# tms-rgb.net
KiCad netlist of a schematic drawn in EAGLE
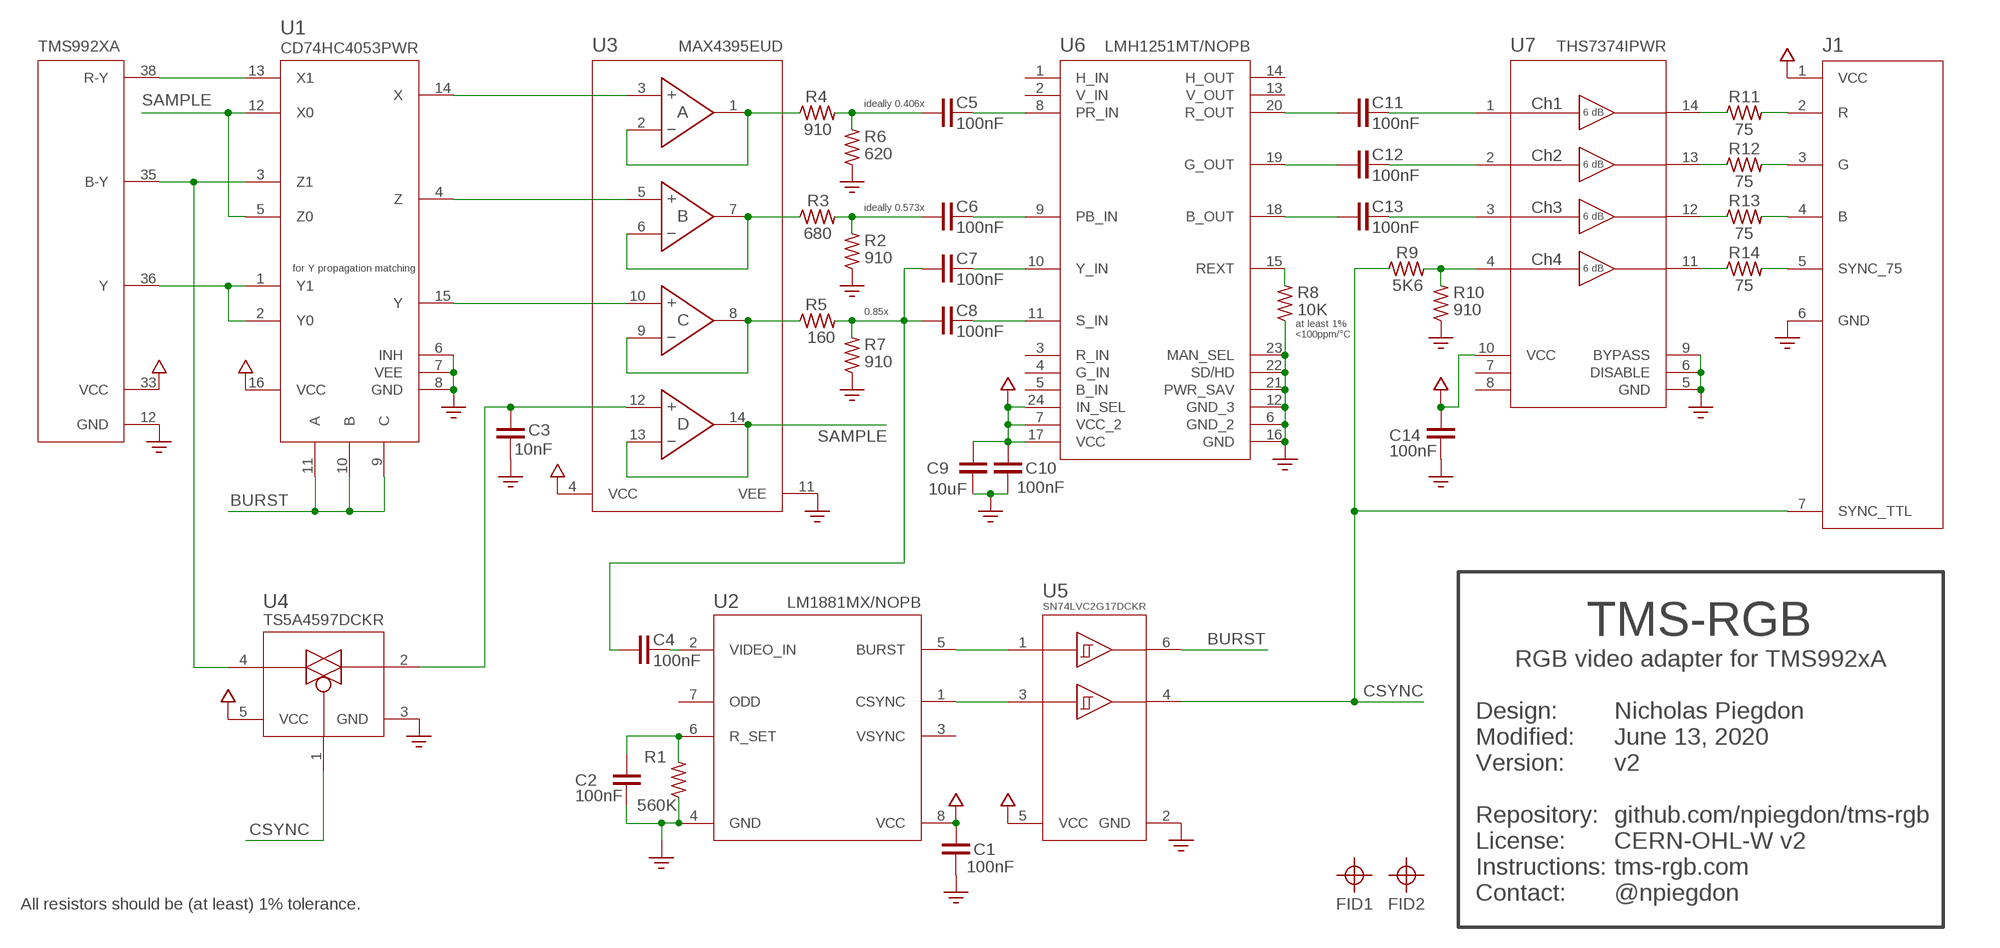
[diagram p0: schematic, sheet 1]

(export (version "E")
  (design (tool "Eeschema 10.0.6"))
  (components
    (comp (ref "C1")
      (value "100nF")
      (footprint "eagle-import:C0603")
      (libsource (lib "eagle-import") (part "C0603"))
    )
    (comp (ref "C2")
      (value "100nF")
      (footprint "eagle-import:C0603")
      (libsource (lib "eagle-import") (part "C0603"))
    )
    (comp (ref "C3")
      (value "10nF")
      (footprint "eagle-import:C0603")
      (libsource (lib "eagle-import") (part "C0603"))
    )
    (comp (ref "C4")
      (value "100nF")
      (footprint "eagle-import:C0603")
      (libsource (lib "eagle-import") (part "C0603"))
    )
    (comp (ref "C5")
      (value "100nF")
      (footprint "eagle-import:C0603")
      (libsource (lib "eagle-import") (part "C0603"))
    )
    (comp (ref "C6")
      (value "100nF")
      (footprint "eagle-import:C0603")
      (libsource (lib "eagle-import") (part "C0603"))
    )
    (comp (ref "C7")
      (value "100nF")
      (footprint "eagle-import:C0603")
      (libsource (lib "eagle-import") (part "C0603"))
    )
    (comp (ref "C8")
      (value "100nF")
      (footprint "eagle-import:C0603")
      (libsource (lib "eagle-import") (part "C0603"))
    )
    (comp (ref "C9")
      (value "10uF")
      (footprint "eagle-import:C1206")
      (libsource (lib "eagle-import") (part "C1206"))
    )
    (comp (ref "C10")
      (value "100nF")
      (footprint "eagle-import:C0603")
      (libsource (lib "eagle-import") (part "C0603"))
    )
    (comp (ref "C11")
      (value "100nF")
      (footprint "eagle-import:C0603")
      (libsource (lib "eagle-import") (part "C0603"))
    )
    (comp (ref "C12")
      (value "100nF")
      (footprint "eagle-import:C0603")
      (libsource (lib "eagle-import") (part "C0603"))
    )
    (comp (ref "C13")
      (value "100nF")
      (footprint "eagle-import:C0603")
      (libsource (lib "eagle-import") (part "C0603"))
    )
    (comp (ref "C14")
      (value "100nF")
      (footprint "eagle-import:C0603")
      (libsource (lib "eagle-import") (part "C0603"))
    )
    (comp (ref "FID1")
      (value "FIDUCIAL")
      (footprint "eagle-import:FIDUCIAL")
      (libsource (lib "eagle-import") (part "FIDUCIAL"))
    )
    (comp (ref "FID2")
      (value "FIDUCIAL")
      (footprint "eagle-import:FIDUCIAL")
      (libsource (lib "eagle-import") (part "FIDUCIAL"))
    )
    (comp (ref "J1")
      (value "Pads")
      (footprint "eagle-import:PADS")
      (libsource (lib "eagle-import") (part "PADSRGB"))
    )
    (comp (ref "R1")
      (value "560K")
      (footprint "eagle-import:R0603")
      (libsource (lib "eagle-import") (part "R0603"))
    )
    (comp (ref "R2")
      (value "910")
      (footprint "eagle-import:R0603")
      (libsource (lib "eagle-import") (part "R0603"))
    )
    (comp (ref "R3")
      (value "680")
      (footprint "eagle-import:R0603")
      (libsource (lib "eagle-import") (part "R0603"))
    )
    (comp (ref "R4")
      (value "910")
      (footprint "eagle-import:R0603")
      (libsource (lib "eagle-import") (part "R0603"))
    )
    (comp (ref "R5")
      (value "160")
      (footprint "eagle-import:R0603")
      (libsource (lib "eagle-import") (part "R0603"))
    )
    (comp (ref "R6")
      (value "620")
      (footprint "eagle-import:R0603")
      (libsource (lib "eagle-import") (part "R0603"))
    )
    (comp (ref "R7")
      (value "910")
      (footprint "eagle-import:R0603")
      (libsource (lib "eagle-import") (part "R0603"))
    )
    (comp (ref "R8")
      (value "10K")
      (footprint "eagle-import:R0603")
      (libsource (lib "eagle-import") (part "R0603"))
    )
    (comp (ref "R9")
      (value "5K6")
      (footprint "eagle-import:R0603")
      (libsource (lib "eagle-import") (part "R0603"))
    )
    (comp (ref "R10")
      (value "910")
      (footprint "eagle-import:R0603")
      (libsource (lib "eagle-import") (part "R0603"))
    )
    (comp (ref "R11")
      (value "75")
      (footprint "eagle-import:R0603")
      (libsource (lib "eagle-import") (part "R0603"))
    )
    (comp (ref "R12")
      (value "75")
      (footprint "eagle-import:R0603")
      (libsource (lib "eagle-import") (part "R0603"))
    )
    (comp (ref "R13")
      (value "75")
      (footprint "eagle-import:R0603")
      (libsource (lib "eagle-import") (part "R0603"))
    )
    (comp (ref "R14")
      (value "75")
      (footprint "eagle-import:R0603")
      (libsource (lib "eagle-import") (part "R0603"))
    )
    (comp (ref "U1")
      (value "CD74HC4053PWR")
      (footprint "eagle-import:CD74HC4053")
      (fields (field (name "MANUFACTURER") "Texas Instruments"))
      (libsource (lib "eagle-import") (part "CD74HC4053PWR"))
    )
    (comp (ref "U2")
      (value "LM1881MX/NOPB")
      (footprint "eagle-import:LM1881")
      (libsource (lib "eagle-import") (part "LM1881MX/NOPB"))
    )
    (comp (ref "U3")
      (value "MAX4395EUD")
      (footprint "eagle-import:MAX4395")
      (fields (field (name "MANUFACTURER_PART_NUMBER") "max4395eud+"))
      (libsource (lib "eagle-import") (part "MAX4395EUD"))
    )
    (comp (ref "U4")
      (value "TS5A4597DCKR")
      (footprint "eagle-import:DCK5")
      (fields
        (field (name "GENERIC_PART_NUMBER") "TS5A4597")
        (field (name "MANUFACTURER") "Texas Instruments")
      )
      (libsource (lib "eagle-import") (part "TS5A4597DCKR"))
    )
    (comp (ref "U5")
      (value "SN74LVC2G17DCKR")
      (footprint "eagle-import:DCK6")
      (fields (field (name "MANUFACTURER") "Texas Instruments"))
      (libsource (lib "eagle-import") (part "SN74LVC2G17DCKR"))
    )
    (comp (ref "U6")
      (value "LMH1251MT/NOPB")
      (footprint "eagle-import:LMH1251")
      (libsource (lib "eagle-import") (part "LMH1251MT/NOPB"))
    )
    (comp (ref "U7")
      (value "THS7374IPWR")
      (footprint "eagle-import:THS7374")
      (fields (field (name "MANUFACTURER") "Texas Instruments"))
      (libsource (lib "eagle-import") (part "THS7374IPWR"))
    )
    (comp (ref "U100")
      (value "TMS992XA")
      (footprint "eagle-import:TMS992XA")
      (libsource (lib "eagle-import") (part "TMS992XA"))
    )
  )
  (nets
    (net (code "1") (name "/BURST") (class "Default")
      (node (ref "U1") (pin "10") (pinfunction "B_10") (pintype "input"))
      (node (ref "U1") (pin "11") (pinfunction "A_11") (pintype "input"))
      (node (ref "U1") (pin "9") (pinfunction "C_9") (pintype "input"))
      (node (ref "U5") (pin "6") (pinfunction "1Y_6") (pintype "output"))
    )
    (net (code "2") (name "/CSYNC") (class "Default")
      (node (ref "J1") (pin "7") (pinfunction "SYNC_TTL_7") (pintype "passive"))
      (node (ref "R9") (pin "1") (pinfunction "1_1") (pintype "passive"))
      (node (ref "U4") (pin "1") (pinfunction "IN_1") (pintype "input"))
      (node (ref "U5") (pin "4") (pinfunction "2Y_4") (pintype "output"))
    )
    (net (code "3") (name "/SAMPLE") (class "Default")
      (node (ref "U1") (pin "12") (pinfunction "X0_12") (pintype "bidirectional"))
      (node (ref "U1") (pin "5") (pinfunction "Z0_5") (pintype "bidirectional"))
      (node (ref "U3") (pin "13") (pinfunction "D-_13") (pintype "input"))
      (node (ref "U3") (pin "14") (pinfunction "D_14") (pintype "output"))
    )
    (net (code "4") (name "5V") (class "Default")
      (node (ref "C1") (pin "1") (pinfunction "1_1") (pintype "passive"))
      (node (ref "C10") (pin "1") (pinfunction "1_1") (pintype "passive"))
      (node (ref "C14") (pin "1") (pinfunction "1_1") (pintype "passive"))
      (node (ref "C9") (pin "1") (pinfunction "1_1") (pintype "passive"))
      (node (ref "J1") (pin "1") (pinfunction "VCC_1") (pintype "passive"))
      (node (ref "U1") (pin "16") (pinfunction "VCC_16") (pintype "power_in"))
      (node (ref "U100") (pin "33") (pinfunction "VCC_33") (pintype "power_in"))
      (node (ref "U2") (pin "8") (pinfunction "VCC_8") (pintype "power_in"))
      (node (ref "U3") (pin "4") (pinfunction "VCC_4") (pintype "power_in"))
      (node (ref "U4") (pin "5") (pinfunction "VCC_5") (pintype "power_in"))
      (node (ref "U5") (pin "5") (pinfunction "VCC_5") (pintype "power_in"))
      (node (ref "U6") (pin "17") (pinfunction "VCC_17") (pintype "passive"))
      (node (ref "U6") (pin "24") (pinfunction "IN_SEL_24") (pintype "input"))
      (node (ref "U6") (pin "7") (pinfunction "VCC_2_7") (pintype "passive"))
      (node (ref "U7") (pin "10") (pinfunction "VCC_10") (pintype "power_in"))
    )
    (net (code "5") (name "GND") (class "Default")
      (node (ref "C1") (pin "2") (pinfunction "2_2") (pintype "passive"))
      (node (ref "C10") (pin "2") (pinfunction "2_2") (pintype "passive"))
      (node (ref "C14") (pin "2") (pinfunction "2_2") (pintype "passive"))
      (node (ref "C2") (pin "2") (pinfunction "2_2") (pintype "passive"))
      (node (ref "C3") (pin "2") (pinfunction "2_2") (pintype "passive"))
      (node (ref "C9") (pin "2") (pinfunction "2_2") (pintype "passive"))
      (node (ref "J1") (pin "6") (pinfunction "GND_6") (pintype "passive"))
      (node (ref "R1") (pin "1") (pinfunction "1_1") (pintype "passive"))
      (node (ref "R10") (pin "1") (pinfunction "1_1") (pintype "passive"))
      (node (ref "R2") (pin "1") (pinfunction "1_1") (pintype "passive"))
      (node (ref "R6") (pin "1") (pinfunction "1_1") (pintype "passive"))
      (node (ref "R7") (pin "1") (pinfunction "1_1") (pintype "passive"))
      (node (ref "R8") (pin "1") (pinfunction "1_1") (pintype "passive"))
      (node (ref "U1") (pin "6") (pinfunction "INH_6") (pintype "input"))
      (node (ref "U1") (pin "7") (pinfunction "VEE_7") (pintype "power_in"))
      (node (ref "U1") (pin "8") (pinfunction "GND_8") (pintype "power_in"))
      (node (ref "U100") (pin "12") (pinfunction "GND_12") (pintype "power_in"))
      (node (ref "U2") (pin "4") (pinfunction "GND_4") (pintype "power_in"))
      (node (ref "U3") (pin "11") (pinfunction "VEE_11") (pintype "power_in"))
      (node (ref "U4") (pin "3") (pinfunction "GND_3") (pintype "power_in"))
      (node (ref "U5") (pin "2") (pinfunction "GND_2") (pintype "power_in"))
      (node (ref "U6") (pin "12") (pinfunction "GND_3_12") (pintype "passive"))
      (node (ref "U6") (pin "16") (pinfunction "GND_16") (pintype "passive"))
      (node (ref "U6") (pin "21") (pinfunction "PWR_SAV_21") (pintype "input"))
      (node (ref "U6") (pin "22") (pinfunction "SD/HD_22") (pintype "input"))
      (node (ref "U6") (pin "23") (pinfunction "MAN_SEL_23") (pintype "input"))
      (node (ref "U6") (pin "6") (pinfunction "GND_2_6") (pintype "passive"))
      (node (ref "U7") (pin "5") (pinfunction "GND_5") (pintype "power_in"))
      (node (ref "U7") (pin "6") (pinfunction "DISABLE_6") (pintype "passive"))
      (node (ref "U7") (pin "9") (pinfunction "BYPASS_9") (pintype "passive"))
    )
    (net (code "6") (name "Net-(C4-Pad1)") (class "Default")
      (node (ref "C4") (pin "1") (pinfunction "1_1") (pintype "passive"))
      (node (ref "C7") (pin "1") (pinfunction "1_1") (pintype "passive"))
      (node (ref "C8") (pin "1") (pinfunction "1_1") (pintype "passive"))
      (node (ref "R5") (pin "2") (pinfunction "2_2") (pintype "passive"))
      (node (ref "R7") (pin "2") (pinfunction "2_2") (pintype "passive"))
    )
    (net (code "7") (name "Net-(C5-Pad1)") (class "Default")
      (node (ref "C5") (pin "1") (pinfunction "1_1") (pintype "passive"))
      (node (ref "R4") (pin "2") (pinfunction "2_2") (pintype "passive"))
      (node (ref "R6") (pin "2") (pinfunction "2_2") (pintype "passive"))
    )
    (net (code "8") (name "Net-(C6-Pad1)") (class "Default")
      (node (ref "C6") (pin "1") (pinfunction "1_1") (pintype "passive"))
      (node (ref "R2") (pin "2") (pinfunction "2_2") (pintype "passive"))
      (node (ref "R3") (pin "2") (pinfunction "2_2") (pintype "passive"))
    )
    (net (code "9") (name "Net-(J1-B)") (class "Default")
      (node (ref "J1") (pin "4") (pinfunction "B_4") (pintype "passive"))
      (node (ref "R13") (pin "2") (pinfunction "2_2") (pintype "passive"))
    )
    (net (code "10") (name "Net-(J1-G)") (class "Default")
      (node (ref "J1") (pin "3") (pinfunction "G_3") (pintype "passive"))
      (node (ref "R12") (pin "2") (pinfunction "2_2") (pintype "passive"))
    )
    (net (code "11") (name "Net-(J1-R)") (class "Default")
      (node (ref "J1") (pin "2") (pinfunction "R_2") (pintype "passive"))
      (node (ref "R11") (pin "2") (pinfunction "2_2") (pintype "passive"))
    )
    (net (code "12") (name "Net-(J1-SYNC_75)") (class "Default")
      (node (ref "J1") (pin "5") (pinfunction "SYNC_75_5") (pintype "passive"))
      (node (ref "R14") (pin "2") (pinfunction "2_2") (pintype "passive"))
    )
    (net (code "13") (name "Net-(U1-X)") (class "Default")
      (node (ref "U1") (pin "14") (pinfunction "X_14") (pintype "bidirectional"))
      (node (ref "U3") (pin "3") (pinfunction "A+_3") (pintype "input"))
    )
    (net (code "14") (name "Net-(U1-X1)") (class "Default")
      (node (ref "U1") (pin "13") (pinfunction "X1_13") (pintype "bidirectional"))
      (node (ref "U100") (pin "38") (pinfunction "R-Y_38") (pintype "output"))
    )
    (net (code "15") (name "Net-(U1-Y)") (class "Default")
      (node (ref "U1") (pin "15") (pinfunction "Y_15") (pintype "bidirectional"))
      (node (ref "U3") (pin "10") (pinfunction "C+_10") (pintype "input"))
    )
    (net (code "16") (name "Net-(U1-Y0)") (class "Default")
      (node (ref "U1") (pin "1") (pinfunction "Y1_1") (pintype "bidirectional"))
      (node (ref "U1") (pin "2") (pinfunction "Y0_2") (pintype "bidirectional"))
      (node (ref "U100") (pin "36") (pinfunction "Y_36") (pintype "output"))
    )
    (net (code "17") (name "Net-(U1-Z)") (class "Default")
      (node (ref "U1") (pin "4") (pinfunction "Z_4") (pintype "bidirectional"))
      (node (ref "U3") (pin "5") (pinfunction "B+_5") (pintype "input"))
    )
    (net (code "18") (name "Net-(U1-Z1)") (class "Default")
      (node (ref "U1") (pin "3") (pinfunction "Z1_3") (pintype "bidirectional"))
      (node (ref "U100") (pin "35") (pinfunction "B-Y_35") (pintype "output"))
      (node (ref "U4") (pin "4") (pinfunction "NC_4") (pintype "passive"))
    )
    (net (code "19") (name "Net-(U2-BURST)") (class "Default")
      (node (ref "U2") (pin "5") (pinfunction "BURST_5") (pintype "output"))
      (node (ref "U5") (pin "1") (pinfunction "1A_1") (pintype "input"))
    )
    (net (code "20") (name "Net-(U2-CSYNC)") (class "Default")
      (node (ref "U2") (pin "1") (pinfunction "CSYNC_1") (pintype "output"))
      (node (ref "U5") (pin "3") (pinfunction "2A_3") (pintype "input"))
    )
    (net (code "21") (name "Net-(U2-R_SET)") (class "Default")
      (node (ref "C2") (pin "1") (pinfunction "1_1") (pintype "passive"))
      (node (ref "R1") (pin "2") (pinfunction "2_2") (pintype "passive"))
      (node (ref "U2") (pin "6") (pinfunction "R_SET_6") (pintype "passive"))
    )
    (net (code "22") (name "Net-(U2-VIDEO_IN)") (class "Default")
      (node (ref "C4") (pin "2") (pinfunction "2_2") (pintype "passive"))
      (node (ref "U2") (pin "2") (pinfunction "VIDEO_IN_2") (pintype "input"))
    )
    (net (code "23") (name "Net-(U3-A)") (class "Default")
      (node (ref "R4") (pin "1") (pinfunction "1_1") (pintype "passive"))
      (node (ref "U3") (pin "1") (pinfunction "A_1") (pintype "output"))
      (node (ref "U3") (pin "2") (pinfunction "A-_2") (pintype "input"))
    )
    (net (code "24") (name "Net-(U3-B)") (class "Default")
      (node (ref "R3") (pin "1") (pinfunction "1_1") (pintype "passive"))
      (node (ref "U3") (pin "6") (pinfunction "B-_6") (pintype "input"))
      (node (ref "U3") (pin "7") (pinfunction "B_7") (pintype "output"))
    )
    (net (code "25") (name "Net-(U3-C)") (class "Default")
      (node (ref "R5") (pin "1") (pinfunction "1_1") (pintype "passive"))
      (node (ref "U3") (pin "8") (pinfunction "C_8") (pintype "output"))
      (node (ref "U3") (pin "9") (pinfunction "C-_9") (pintype "input"))
    )
    (net (code "26") (name "Net-(U3-D+)") (class "Default")
      (node (ref "C3") (pin "1") (pinfunction "1_1") (pintype "passive"))
      (node (ref "U3") (pin "12") (pinfunction "D+_12") (pintype "input"))
      (node (ref "U4") (pin "2") (pinfunction "COM_2") (pintype "passive"))
    )
    (net (code "27") (name "Net-(U6-B_OUT)") (class "Default")
      (node (ref "C13") (pin "1") (pinfunction "1_1") (pintype "passive"))
      (node (ref "U6") (pin "18") (pinfunction "B_OUT_18") (pintype "output"))
    )
    (net (code "28") (name "Net-(U6-G_OUT)") (class "Default")
      (node (ref "C12") (pin "1") (pinfunction "1_1") (pintype "passive"))
      (node (ref "U6") (pin "19") (pinfunction "G_OUT_19") (pintype "output"))
    )
    (net (code "29") (name "Net-(U6-PB_IN)") (class "Default")
      (node (ref "C6") (pin "2") (pinfunction "2_2") (pintype "passive"))
      (node (ref "U6") (pin "9") (pinfunction "PB_IN_9") (pintype "input"))
    )
    (net (code "30") (name "Net-(U6-PR_IN)") (class "Default")
      (node (ref "C5") (pin "2") (pinfunction "2_2") (pintype "passive"))
      (node (ref "U6") (pin "8") (pinfunction "PR_IN_8") (pintype "input"))
    )
    (net (code "31") (name "Net-(U6-REXT)") (class "Default")
      (node (ref "R8") (pin "2") (pinfunction "2_2") (pintype "passive"))
      (node (ref "U6") (pin "15") (pinfunction "REXT_15") (pintype "passive"))
    )
    (net (code "32") (name "Net-(U6-R_OUT)") (class "Default")
      (node (ref "C11") (pin "1") (pinfunction "1_1") (pintype "passive"))
      (node (ref "U6") (pin "20") (pinfunction "R_OUT_20") (pintype "output"))
    )
    (net (code "33") (name "Net-(U6-S_IN)") (class "Default")
      (node (ref "C8") (pin "2") (pinfunction "2_2") (pintype "passive"))
      (node (ref "U6") (pin "11") (pinfunction "S_IN_11") (pintype "input"))
    )
    (net (code "34") (name "Net-(U6-Y_IN)") (class "Default")
      (node (ref "C7") (pin "2") (pinfunction "2_2") (pintype "passive"))
      (node (ref "U6") (pin "10") (pinfunction "Y_IN_10") (pintype "input"))
    )
    (net (code "35") (name "Net-(U7-CH1IN)") (class "Default")
      (node (ref "C11") (pin "2") (pinfunction "2_2") (pintype "passive"))
      (node (ref "U7") (pin "1") (pinfunction "CH1IN_1") (pintype "input"))
    )
    (net (code "36") (name "Net-(U7-CH1OUT)") (class "Default")
      (node (ref "R11") (pin "1") (pinfunction "1_1") (pintype "passive"))
      (node (ref "U7") (pin "14") (pinfunction "CH1OUT_14") (pintype "output"))
    )
    (net (code "37") (name "Net-(U7-CH2IN)") (class "Default")
      (node (ref "C12") (pin "2") (pinfunction "2_2") (pintype "passive"))
      (node (ref "U7") (pin "2") (pinfunction "CH2IN_2") (pintype "input"))
    )
    (net (code "38") (name "Net-(U7-CH2OUT)") (class "Default")
      (node (ref "R12") (pin "1") (pinfunction "1_1") (pintype "passive"))
      (node (ref "U7") (pin "13") (pinfunction "CH2OUT_13") (pintype "output"))
    )
    (net (code "39") (name "Net-(U7-CH3IN)") (class "Default")
      (node (ref "C13") (pin "2") (pinfunction "2_2") (pintype "passive"))
      (node (ref "U7") (pin "3") (pinfunction "CH3IN_3") (pintype "input"))
    )
    (net (code "40") (name "Net-(U7-CH3OUT)") (class "Default")
      (node (ref "R13") (pin "1") (pinfunction "1_1") (pintype "passive"))
      (node (ref "U7") (pin "12") (pinfunction "CH3OUT_12") (pintype "output"))
    )
    (net (code "41") (name "Net-(U7-CH4IN)") (class "Default")
      (node (ref "R10") (pin "2") (pinfunction "2_2") (pintype "passive"))
      (node (ref "R9") (pin "2") (pinfunction "2_2") (pintype "passive"))
      (node (ref "U7") (pin "4") (pinfunction "CH4IN_4") (pintype "input"))
    )
    (net (code "42") (name "Net-(U7-CH4OUT)") (class "Default")
      (node (ref "R14") (pin "1") (pinfunction "1_1") (pintype "passive"))
      (node (ref "U7") (pin "11") (pinfunction "CH4OUT_11") (pintype "output"))
    )
    (net (code "43") (name "unconnected-(U2-ODD-Pad7)") (class "Default")
      (node (ref "U2") (pin "7") (pinfunction "ODD_7") (pintype "output"))
    )
    (net (code "44") (name "unconnected-(U2-VSYNC-Pad3)") (class "Default")
      (node (ref "U2") (pin "3") (pinfunction "VSYNC_3") (pintype "output"))
    )
    (net (code "45") (name "unconnected-(U6-B_IN-Pad5)") (class "Default")
      (node (ref "U6") (pin "5") (pinfunction "B_IN_5") (pintype "passive"))
    )
    (net (code "46") (name "unconnected-(U6-G_IN-Pad4)") (class "Default")
      (node (ref "U6") (pin "4") (pinfunction "G_IN_4") (pintype "passive"))
    )
    (net (code "47") (name "unconnected-(U6-H_IN-Pad1)") (class "Default")
      (node (ref "U6") (pin "1") (pinfunction "H_IN_1") (pintype "passive"))
    )
    (net (code "48") (name "unconnected-(U6-H_OUT-Pad14)") (class "Default")
      (node (ref "U6") (pin "14") (pinfunction "H_OUT_14") (pintype "output"))
    )
    (net (code "49") (name "unconnected-(U6-R_IN-Pad3)") (class "Default")
      (node (ref "U6") (pin "3") (pinfunction "R_IN_3") (pintype "passive"))
    )
    (net (code "50") (name "unconnected-(U6-V_IN-Pad2)") (class "Default")
      (node (ref "U6") (pin "2") (pinfunction "V_IN_2") (pintype "passive"))
    )
    (net (code "51") (name "unconnected-(U6-V_OUT-Pad13)") (class "Default")
      (node (ref "U6") (pin "13") (pinfunction "V_OUT_13") (pintype "output"))
    )
    (net (code "52") (name "unconnected-(U7-NC-Pad8)") (class "Default")
      (node (ref "U7") (pin "8") (pinfunction "NC_8") (pintype "no_connect"))
    )
    (net (code "53") (name "unconnected-(U7-NC_2-Pad7)") (class "Default")
      (node (ref "U7") (pin "7") (pinfunction "NC_2_7") (pintype "no_connect"))
    )
  )
)
